# afron_shield.net
KiCad netlist of a schematic drawn in EAGLE
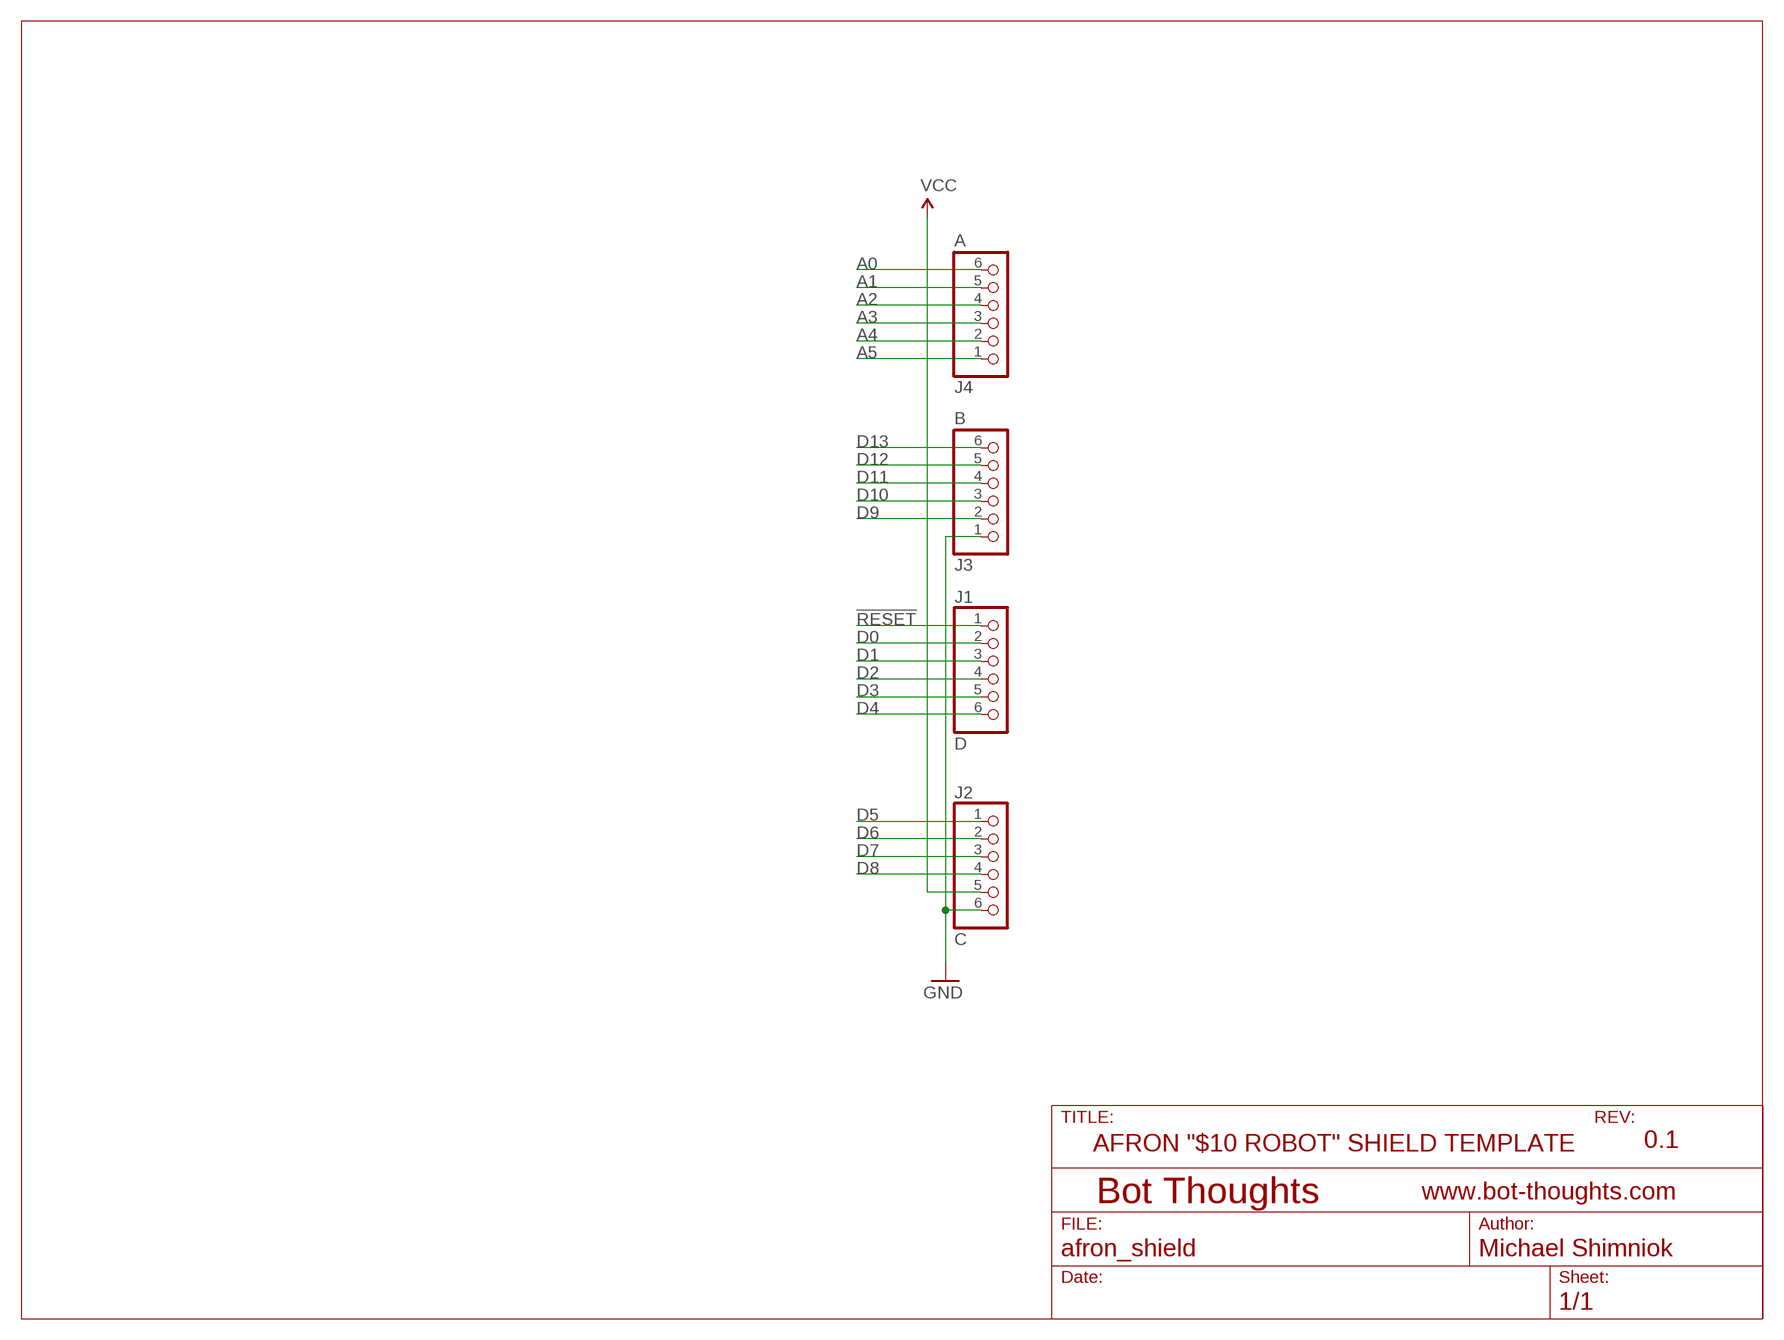
[diagram p0: schematic, sheet 1]

(export (version "E")
  (design (tool "Eeschema 10.0.6"))
  (components
    (comp (ref "J1")
      (value "D")
      (footprint "eagle-import:1X06-S")
      (libsource (lib "eagle-import") (part "PINHD-1X06_2.54-S"))
    )
    (comp (ref "J2")
      (value "C")
      (footprint "eagle-import:1X06-S")
      (libsource (lib "eagle-import") (part "PINHD-1X06_2.54-S"))
    )
    (comp (ref "J3")
      (value "B")
      (footprint "eagle-import:1X06-S")
      (libsource (lib "eagle-import") (part "PINHD-1X06_2.54-S"))
    )
    (comp (ref "J4")
      (value "A")
      (footprint "eagle-import:1X06-S")
      (libsource (lib "eagle-import") (part "PINHD-1X06_2.54-S"))
    )
  )
  (nets
    (net (code "1") (name "/A0") (class "Default")
      (node (ref "J4") (pin "6") (pinfunction "6_6") (pintype "passive"))
    )
    (net (code "2") (name "/A1") (class "Default")
      (node (ref "J4") (pin "5") (pinfunction "5_5") (pintype "passive"))
    )
    (net (code "3") (name "/A2") (class "Default")
      (node (ref "J4") (pin "4") (pinfunction "4_4") (pintype "passive"))
    )
    (net (code "4") (name "/A3") (class "Default")
      (node (ref "J4") (pin "3") (pinfunction "3_3") (pintype "passive"))
    )
    (net (code "5") (name "/A4") (class "Default")
      (node (ref "J4") (pin "2") (pinfunction "2_2") (pintype "passive"))
    )
    (net (code "6") (name "/A5") (class "Default")
      (node (ref "J4") (pin "1") (pinfunction "1_1") (pintype "passive"))
    )
    (net (code "7") (name "/D0") (class "Default")
      (node (ref "J1") (pin "2") (pinfunction "2_2") (pintype "passive"))
    )
    (net (code "8") (name "/D1") (class "Default")
      (node (ref "J1") (pin "3") (pinfunction "3_3") (pintype "passive"))
    )
    (net (code "9") (name "/D2") (class "Default")
      (node (ref "J1") (pin "4") (pinfunction "4_4") (pintype "passive"))
    )
    (net (code "10") (name "/D3") (class "Default")
      (node (ref "J1") (pin "5") (pinfunction "5_5") (pintype "passive"))
    )
    (net (code "11") (name "/D4") (class "Default")
      (node (ref "J1") (pin "6") (pinfunction "6_6") (pintype "passive"))
    )
    (net (code "12") (name "/D5") (class "Default")
      (node (ref "J2") (pin "1") (pinfunction "1_1") (pintype "passive"))
    )
    (net (code "13") (name "/D6") (class "Default")
      (node (ref "J2") (pin "2") (pinfunction "2_2") (pintype "passive"))
    )
    (net (code "14") (name "/D7") (class "Default")
      (node (ref "J2") (pin "3") (pinfunction "3_3") (pintype "passive"))
    )
    (net (code "15") (name "/D8") (class "Default")
      (node (ref "J2") (pin "4") (pinfunction "4_4") (pintype "passive"))
    )
    (net (code "16") (name "/D9") (class "Default")
      (node (ref "J3") (pin "2") (pinfunction "2_2") (pintype "passive"))
    )
    (net (code "17") (name "/D10") (class "Default")
      (node (ref "J3") (pin "3") (pinfunction "3_3") (pintype "passive"))
    )
    (net (code "18") (name "/D11") (class "Default")
      (node (ref "J3") (pin "4") (pinfunction "4_4") (pintype "passive"))
    )
    (net (code "19") (name "/D12") (class "Default")
      (node (ref "J3") (pin "5") (pinfunction "5_5") (pintype "passive"))
    )
    (net (code "20") (name "/D13") (class "Default")
      (node (ref "J3") (pin "6") (pinfunction "6_6") (pintype "passive"))
    )
    (net (code "21") (name "/~{RESET}") (class "Default")
      (node (ref "J1") (pin "1") (pinfunction "1_1") (pintype "passive"))
    )
    (net (code "22") (name "GND") (class "Default")
      (node (ref "J2") (pin "6") (pinfunction "6_6") (pintype "passive"))
      (node (ref "J3") (pin "1") (pinfunction "1_1") (pintype "passive"))
    )
    (net (code "23") (name "VCC") (class "Default")
      (node (ref "J2") (pin "5") (pinfunction "5_5") (pintype "passive"))
    )
  )
)
